# Buck-converter-controller.net
KiCad netlist of a schematic drawn in Altium Designer
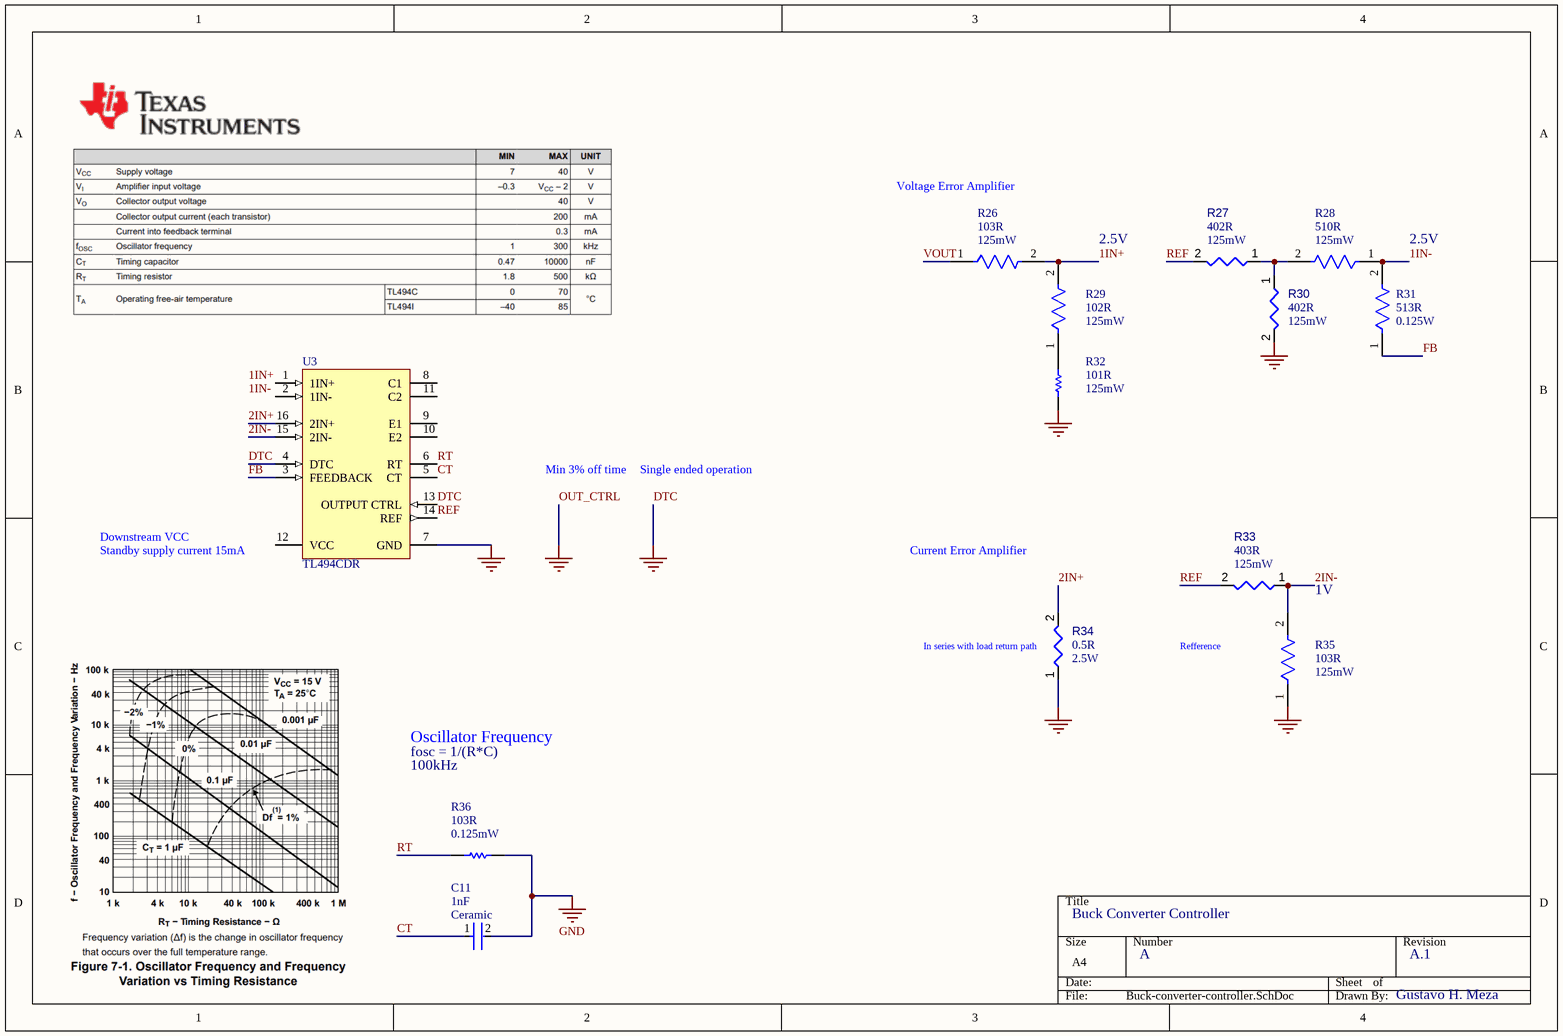
[diagram p0: Buck-converter-controller.SchDoc]

(export (version "E")
  (design (tool "Eeschema 10.0.6"))
  (components
    (comp (ref "C11")
      (value "08051A102JAT2A")
      (footprint "FP-0805-L_2_01_0_2-W_1_25-MFG")
      (description "General Purpose Ceramic Capacitor, 0805, 1nF, 5%, C0G, 30ppm/°C, 100V")
      (fields
        (field (name "VOLTAGE") "100V")
        (field (name "CAPACITANCE") "1nF")
        (field (name "TOLERANCE") "5%")
        (field (name "DIELECTRIC MATERIAL") "Ceramic")
      )
      (libsource (lib "Altium Content Vault") (part "02cd4be3c70576c341d710602a673aa"))
    )
    (comp (ref "R26")
      (value "CRCW080510K0FKEA")
      (footprint "FP-CRCW0805-e3-IPC_A")
      (description "RES Thick Film, 10kΩ, 1%, 0.125W, 100ppm/°C, 0805")
      (fields
        (field (name "RESISTANCE") "103R")
        (field (name "TOLERANCE") "1%")
        (field (name "POWER RATING") "125mW")
      )
      (libsource (lib "Altium Content Vault") (part "1029c3af85768c4190bb7ad29bc67b5"))
    )
    (comp (ref "R27")
      (value "402R")
      (footprint "RESC3416X05N")
      (description "RES SMD 4K OHM 1% 1/8W 0805")
      (fields
        (field (name "POWER") "125mW")
        (field (name "TOLERANCE") "1%")
        (field (name "Comment") "CRCW08054K00FKTA")
      )
      (libsource (lib "Cetys University") (part "RES-2"))
    )
    (comp (ref "R28")
      (value "CR0805JW511E")
      (footprint "FP-CR0805-IPC_B")
      (description "Thick Film Chip Resistors 0805 510Ω 0.125W 5% 200ppm/°C")
      (fields
        (field (name "RESISTANCE") "510R")
        (field (name "POWER RATING") "125mW")
        (field (name "TOLERANCE") "5%")
      )
      (libsource (lib "Altium Content Vault") (part "1029c3af85768c4190bb7ad29bc67b5"))
    )
    (comp (ref "R29")
      (value "CRCW08051K00JNEA")
      (footprint "FP-CRCW0805-e3-IPC_B")
      (description "RES Thick Film, 1kΩ, 5%, 0.125W, 200ppm/°C, 0805")
      (fields
        (field (name "POWER RATING") "125mW")
        (field (name "RESISTANCE") "102R")
        (field (name "TOLERANCE") "5%")
      )
      (libsource (lib "Altium Content Vault") (part "1029c3af85768c4190bb7ad29bc67b5"))
    )
    (comp (ref "R30")
      (value "402R")
      (footprint "RESC3416X05N")
      (description "RES SMD 4K OHM 1% 1/8W 0805")
      (fields
        (field (name "POWER") "125mW")
        (field (name "TOLERANCE") "1%")
        (field (name "Comment") "CRCW08054K00FKTA")
      )
      (libsource (lib "Cetys University") (part "RES-2"))
    )
    (comp (ref "R31")
      (value "513R")
      (footprint "FP-RT0805-MFG")
      (description "RES SMD 51K OHM 0.1% 1/8W 0805")
      (fields
        (field (name "MANUFACTURER") "Yageo")
        (field (name "TOLERANCE") "0.0025")
        (field (name "POWER RATING") "0.125W")
      )
      (libsource (lib "Altium Content Vault") (part "1029c3af85768c4190bb7ad29bc67b5"))
    )
    (comp (ref "R32")
      (value "ERA6AEB101V")
      (footprint "RESC2013X60X40ML20T25")
      (fields
        (field (name "MANUFACTURER") "Panasonic")
        (field (name "RESISTANCEMETER 1") "101R")
        (field (name "POWER") "125mW")
      )
      (libsource (lib "Altium Content Vault") (part "RES"))
    )
    (comp (ref "R33")
      (value "403R")
      (footprint "RESC3416X05N")
      (description "RES SMD 4K OHM 1% 1/8W 0805")
      (fields
        (field (name "POWER") "125mW")
        (field (name "TOLERANCE") "1%")
        (field (name "Comment") "CRCW08054K00FKTA")
      )
      (libsource (lib "Cetys University") (part "RES-2"))
    )
    (comp (ref "R34")
      (value "0.5R")
      (footprint "RS02CR5000FB12-Footprint-1")
      (description "Fixed Resistor, Wire Wound, 2.5W, 0.5ohm, 1% +/-Tol, 90ppm/Cel, Through Hole Mount")
      (fields
        (field (name "TOLERANCE") "1%")
        (field (name "POWER") "2.5W")
        (field (name "Comment") "RS02CR5000FB12")
      )
      (libsource (lib "Cetys University") (part "RES-2"))
    )
    (comp (ref "R35")
      (value "ERA6AEB102V")
      (footprint "FP-ERA6A-IPC_C")
      (description "RES 1K OHM 0.1% 1/8W 0805")
      (fields
        (field (name "RESISTANCE") "103R")
        (field (name "MAX POWER DISSIPATION") "125mW")
        (field (name "TOLERANCE") "0.1%")
      )
      (libsource (lib "Altium Content Vault") (part "1029c3af85768c4190bb7ad29bc67b5"))
    )
    (comp (ref "R36")
      (value "RC0805JR-0710KL")
      (footprint "RESC2013X60X35ML10T20")
      (description "Chip Resistor, 10 KOhm, +/- 5%, 0.125 W, -55 to 155 degC, 0805 (2012 Metric), RoHS, Tape and Reel")
      (fields
        (field (name "MANUFACTURER") "Yageo")
        (field (name "RESISTANCE") "103R")
        (field (name "POWER") "0.125mW")
      )
      (libsource (lib "Altium Content Vault") (part "RES-2"))
    )
    (comp (ref "U3")
      (value "TL494CDR")
      (footprint "D0016A_N")
      (fields (field (name "MANUFACTURER") "Texas Instruments"))
      (libsource (lib "Altium Content Vault") (part "TI-494D16"))
    )
  )
  (nets
    (net (code "1") (name "/1IN+") (class "Default")
      (node (ref "R26") (pin "2") (pinfunction "2_2") (pintype "passive"))
      (node (ref "R29") (pin "2") (pinfunction "2_2") (pintype "passive"))
    )
    (net (code "2") (name "/1IN-") (class "Default")
      (node (ref "R28") (pin "1") (pinfunction "1_1") (pintype "passive"))
      (node (ref "R31") (pin "2") (pinfunction "2_2") (pintype "passive"))
    )
    (net (code "3") (name "/2IN+") (class "Default")
      (node (ref "R34") (pin "2") (pinfunction "2_2") (pintype "passive"))
      (node (ref "U3") (pin "16") (pinfunction "2IN+_16") (pintype "input"))
    )
    (net (code "4") (name "/2IN-") (class "Default")
      (node (ref "R33") (pin "1") (pinfunction "1_1") (pintype "passive"))
      (node (ref "R35") (pin "2") (pinfunction "2_2") (pintype "passive"))
      (node (ref "U3") (pin "15") (pinfunction "2IN-_15") (pintype "input"))
    )
    (net (code "5") (name "/CT") (class "Default")
      (node (ref "C11") (pin "1") (pinfunction "1_1") (pintype "passive"))
      (node (ref "U3") (pin "5") (pinfunction "CT_5") (pintype "passive"))
    )
    (net (code "6") (name "/FB") (class "Default")
      (node (ref "R31") (pin "1") (pinfunction "1_1") (pintype "passive"))
      (node (ref "U3") (pin "3") (pinfunction "FEEDBACK_3") (pintype "input"))
    )
    (net (code "7") (name "/REF") (class "Default")
      (node (ref "R27") (pin "2") (pinfunction "2_2") (pintype "passive"))
      (node (ref "R33") (pin "2") (pinfunction "2_2") (pintype "passive"))
      (node (ref "U3") (pin "14") (pinfunction "REF_14") (pintype "output"))
    )
    (net (code "8") (name "/RT") (class "Default")
      (node (ref "R36") (pin "1") (pinfunction "1_1") (pintype "passive"))
      (node (ref "U3") (pin "6") (pinfunction "RT_6") (pintype "passive"))
    )
    (net (code "9") (name "/VOUT") (class "Default")
      (node (ref "R26") (pin "1") (pinfunction "1_1") (pintype "passive"))
    )
    (net (code "10") (name "GND") (class "Default")
      (node (ref "C11") (pin "2") (pinfunction "2_2") (pintype "passive"))
      (node (ref "R30") (pin "2") (pinfunction "2_2") (pintype "passive"))
      (node (ref "R32") (pin "1") (pinfunction "1_1") (pintype "passive"))
      (node (ref "R34") (pin "1") (pinfunction "1_1") (pintype "passive"))
      (node (ref "R35") (pin "1") (pinfunction "1_1") (pintype "passive"))
      (node (ref "R36") (pin "2") (pinfunction "2_2") (pintype "passive"))
      (node (ref "U3") (pin "13") (pinfunction "OUTPUT_CTRL_13") (pintype "input"))
      (node (ref "U3") (pin "4") (pinfunction "DTC_4") (pintype "input"))
      (node (ref "U3") (pin "7") (pinfunction "GND_7") (pintype "power_in"))
    )
    (net (code "11") (name "Net-(R27-Pad1)") (class "Default")
      (node (ref "R27") (pin "1") (pinfunction "1_1") (pintype "passive"))
      (node (ref "R28") (pin "2") (pinfunction "2_2") (pintype "passive"))
      (node (ref "R30") (pin "1") (pinfunction "1_1") (pintype "passive"))
    )
    (net (code "12") (name "Net-(R29-Pad1)") (class "Default")
      (node (ref "R29") (pin "1") (pinfunction "1_1") (pintype "passive"))
      (node (ref "R32") (pin "2") (pinfunction "2_2") (pintype "passive"))
    )
    (net (code "13") (name "unconnected-(U3-1IN+-Pad1)") (class "Default")
      (node (ref "U3") (pin "1") (pinfunction "1IN+_1") (pintype "input"))
    )
    (net (code "14") (name "unconnected-(U3-1IN--Pad2)") (class "Default")
      (node (ref "U3") (pin "2") (pinfunction "1IN-_2") (pintype "input"))
    )
    (net (code "15") (name "unconnected-(U3-C1-Pad8)") (class "Default")
      (node (ref "U3") (pin "8") (pinfunction "C1_8") (pintype "passive"))
    )
    (net (code "16") (name "unconnected-(U3-C2-Pad11)") (class "Default")
      (node (ref "U3") (pin "11") (pinfunction "C2_11") (pintype "passive"))
    )
    (net (code "17") (name "unconnected-(U3-E1-Pad9)") (class "Default")
      (node (ref "U3") (pin "9") (pinfunction "E1_9") (pintype "passive"))
    )
    (net (code "18") (name "unconnected-(U3-E2-Pad10)") (class "Default")
      (node (ref "U3") (pin "10") (pinfunction "E2_10") (pintype "passive"))
    )
    (net (code "19") (name "unconnected-(U3-VCC-Pad12)") (class "Default")
      (node (ref "U3") (pin "12") (pinfunction "VCC_12") (pintype "power_in"))
    )
  )
)
